# AnalogADCs.net
KiCad netlist of a schematic drawn in Altium Designer
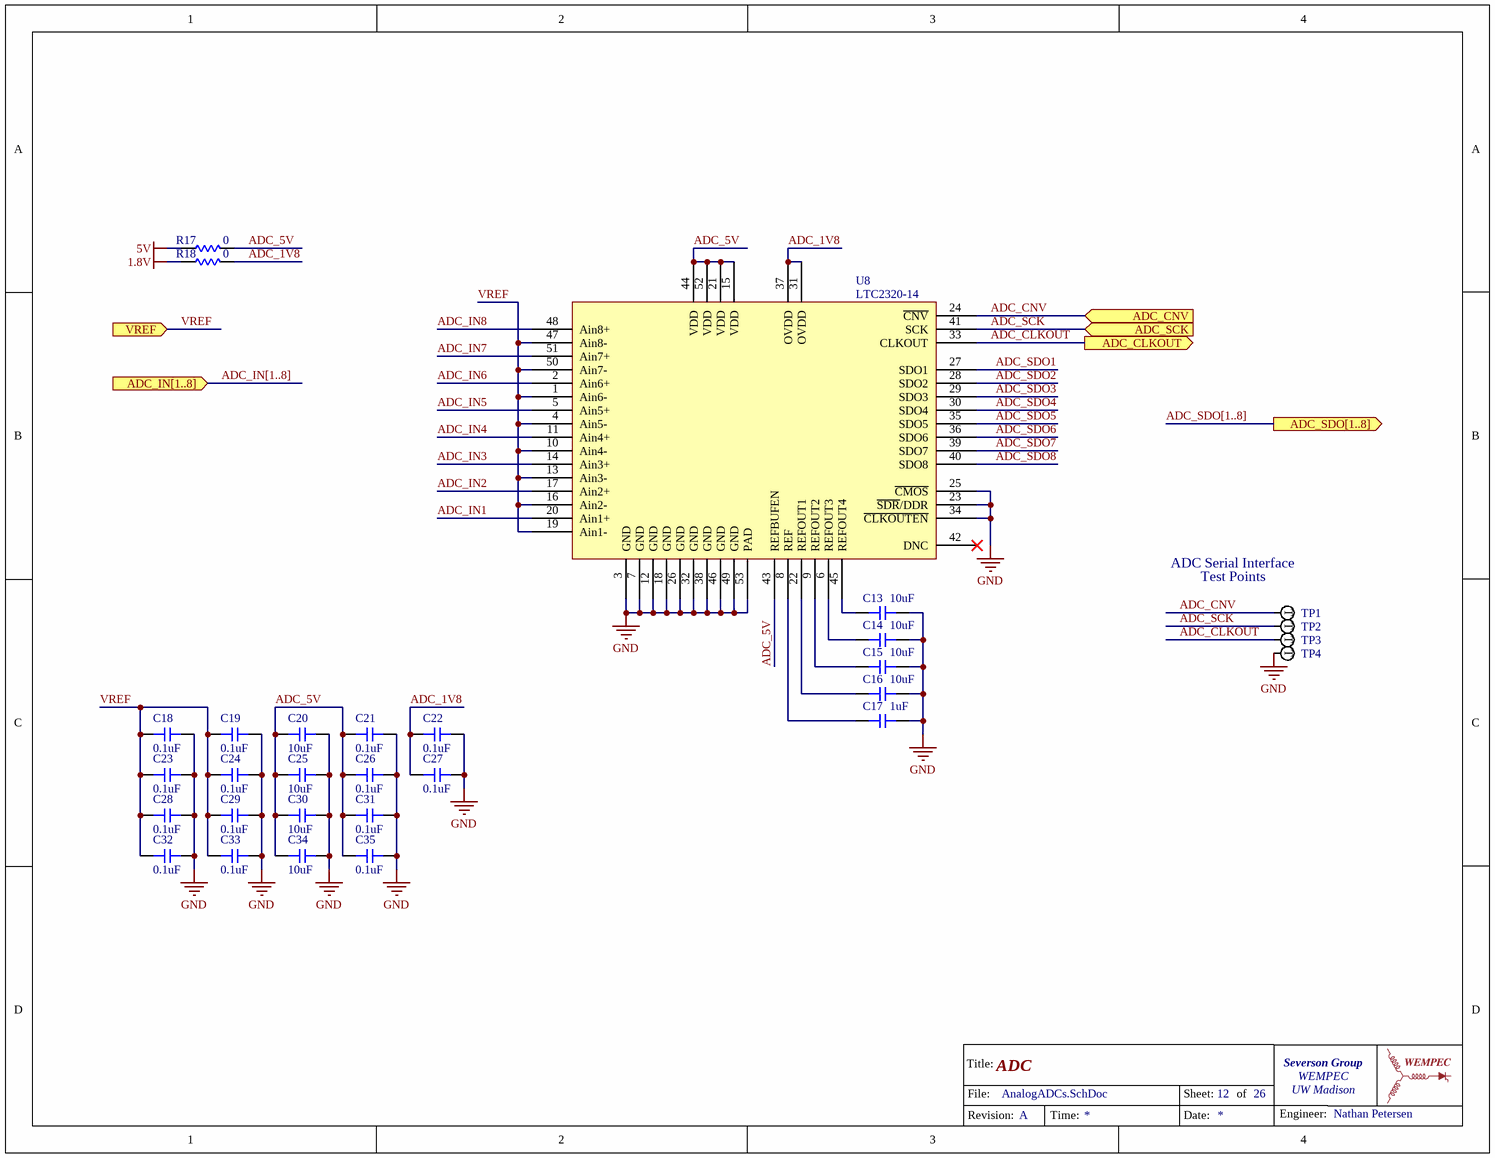
[diagram p0: AnalogADCs.SchDoc]

(export (version "E")
  (design (tool "Eeschema 10.0.6"))
  (components
    (comp (ref "C13")
      (value "10uF")
      (footprint "AMDC:0603-CAP")
      (description "Capacitor")
      (libsource (lib "AMDC") (part "Capacitor"))
    )
    (comp (ref "C14")
      (value "10uF")
      (footprint "AMDC:0603-CAP")
      (description "Capacitor")
      (libsource (lib "AMDC") (part "Capacitor"))
    )
    (comp (ref "C15")
      (value "10uF")
      (footprint "AMDC:0603-CAP")
      (description "Capacitor")
      (libsource (lib "AMDC") (part "Capacitor"))
    )
    (comp (ref "C16")
      (value "10uF")
      (footprint "AMDC:0603-CAP")
      (description "Capacitor")
      (libsource (lib "AMDC") (part "Capacitor"))
    )
    (comp (ref "C17")
      (value "1uF")
      (footprint "AMDC:0603-CAP")
      (description "Capacitor")
      (libsource (lib "AMDC") (part "Capacitor"))
    )
    (comp (ref "C18")
      (value "0.1uF")
      (footprint "AMDC:0603-CAP")
      (description "Capacitor")
      (libsource (lib "AMDC") (part "Capacitor"))
    )
    (comp (ref "C19")
      (value "0.1uF")
      (footprint "AMDC:0603-CAP")
      (description "Capacitor")
      (libsource (lib "AMDC") (part "Capacitor"))
    )
    (comp (ref "C20")
      (value "10uF")
      (footprint "AMDC:0603-CAP")
      (description "Capacitor")
      (libsource (lib "AMDC") (part "Capacitor"))
    )
    (comp (ref "C21")
      (value "0.1uF")
      (footprint "AMDC:0603-CAP")
      (description "Capacitor")
      (libsource (lib "AMDC") (part "Capacitor"))
    )
    (comp (ref "C22")
      (value "0.1uF")
      (footprint "AMDC:0603-CAP")
      (description "Capacitor")
      (libsource (lib "AMDC") (part "Capacitor"))
    )
    (comp (ref "C23")
      (value "0.1uF")
      (footprint "AMDC:0603-CAP")
      (description "Capacitor")
      (libsource (lib "AMDC") (part "Capacitor"))
    )
    (comp (ref "C24")
      (value "0.1uF")
      (footprint "AMDC:0603-CAP")
      (description "Capacitor")
      (libsource (lib "AMDC") (part "Capacitor"))
    )
    (comp (ref "C25")
      (value "10uF")
      (footprint "AMDC:0603-CAP")
      (description "Capacitor")
      (libsource (lib "AMDC") (part "Capacitor"))
    )
    (comp (ref "C26")
      (value "0.1uF")
      (footprint "AMDC:0603-CAP")
      (description "Capacitor")
      (libsource (lib "AMDC") (part "Capacitor"))
    )
    (comp (ref "C27")
      (value "0.1uF")
      (footprint "AMDC:0603-CAP")
      (description "Capacitor")
      (libsource (lib "AMDC") (part "Capacitor"))
    )
    (comp (ref "C28")
      (value "0.1uF")
      (footprint "AMDC:0603-CAP")
      (description "Capacitor")
      (libsource (lib "AMDC") (part "Capacitor"))
    )
    (comp (ref "C29")
      (value "0.1uF")
      (footprint "AMDC:0603-CAP")
      (description "Capacitor")
      (libsource (lib "AMDC") (part "Capacitor"))
    )
    (comp (ref "C30")
      (value "10uF")
      (footprint "AMDC:0603-CAP")
      (description "Capacitor")
      (libsource (lib "AMDC") (part "Capacitor"))
    )
    (comp (ref "C31")
      (value "0.1uF")
      (footprint "AMDC:0603-CAP")
      (description "Capacitor")
      (libsource (lib "AMDC") (part "Capacitor"))
    )
    (comp (ref "C32")
      (value "0.1uF")
      (footprint "AMDC:0603-CAP")
      (description "Capacitor")
      (libsource (lib "AMDC") (part "Capacitor"))
    )
    (comp (ref "C33")
      (value "0.1uF")
      (footprint "AMDC:0603-CAP")
      (description "Capacitor")
      (libsource (lib "AMDC") (part "Capacitor"))
    )
    (comp (ref "C34")
      (value "10uF")
      (footprint "AMDC:0603-CAP")
      (description "Capacitor")
      (libsource (lib "AMDC") (part "Capacitor"))
    )
    (comp (ref "C35")
      (value "0.1uF")
      (footprint "AMDC:0603-CAP")
      (description "Capacitor")
      (libsource (lib "AMDC") (part "Capacitor"))
    )
    (comp (ref "R17")
      (value "0")
      (footprint "AMDC:1206-RES")
      (description "Resistor")
      (libsource (lib "AMDC") (part "Resistor"))
    )
    (comp (ref "R18")
      (value "0")
      (footprint "AMDC:1206-RES")
      (description "Resistor")
      (libsource (lib "AMDC") (part "Resistor"))
    )
    (comp (ref "TP1")
      (value "Test Point")
      (footprint "AMDC:RCU-0C")
      (libsource (lib "AMDC") (part "Test Point"))
    )
    (comp (ref "TP2")
      (value "Test Point")
      (footprint "AMDC:RCU-0C")
      (libsource (lib "AMDC") (part "Test Point"))
    )
    (comp (ref "TP3")
      (value "Test Point")
      (footprint "AMDC:RCU-0C")
      (libsource (lib "AMDC") (part "Test Point"))
    )
    (comp (ref "TP4")
      (value "Test Point")
      (footprint "AMDC:RCU-0C")
      (libsource (lib "AMDC") (part "Test Point"))
    )
    (comp (ref "U8")
      (value "LTC2320-14")
      (footprint "AMDC:QFN50P700X800X80_HS-53N")
      (description "IC ADC 14BIT 1.5MSPS SAR 52QFN - 14 Bit Analog to Digital Converter 8 Input 4 SAR 52-QFN (7x8)")
      (libsource (lib "AMDC") (part "LTC2320-14"))
    )
  )
  (nets
    (net (code "1") (name "/ADC_1V8") (class "Default")
      (node (ref "C22") (pin "1") (pinfunction "1_1") (pintype "passive"))
      (node (ref "C27") (pin "1") (pinfunction "1_1") (pintype "passive"))
      (node (ref "R18") (pin "2") (pinfunction "2_2") (pintype "passive"))
      (node (ref "U8") (pin "31") (pinfunction "OVDD_31") (pintype "passive"))
      (node (ref "U8") (pin "37") (pinfunction "OVDD_37") (pintype "passive"))
    )
    (net (code "2") (name "/ADC_5V") (class "Default")
      (node (ref "C20") (pin "1") (pinfunction "1_1") (pintype "passive"))
      (node (ref "C21") (pin "1") (pinfunction "1_1") (pintype "passive"))
      (node (ref "C25") (pin "1") (pinfunction "1_1") (pintype "passive"))
      (node (ref "C26") (pin "1") (pinfunction "1_1") (pintype "passive"))
      (node (ref "C30") (pin "1") (pinfunction "1_1") (pintype "passive"))
      (node (ref "C31") (pin "1") (pinfunction "1_1") (pintype "passive"))
      (node (ref "C34") (pin "1") (pinfunction "1_1") (pintype "passive"))
      (node (ref "C35") (pin "1") (pinfunction "1_1") (pintype "passive"))
      (node (ref "R17") (pin "2") (pinfunction "2_2") (pintype "passive"))
      (node (ref "U8") (pin "15") (pinfunction "VDD_15") (pintype "passive"))
      (node (ref "U8") (pin "21") (pinfunction "VDD_21") (pintype "passive"))
      (node (ref "U8") (pin "43") (pinfunction "REFBUFEN_43") (pintype "passive"))
      (node (ref "U8") (pin "44") (pinfunction "VDD_44") (pintype "passive"))
      (node (ref "U8") (pin "52") (pinfunction "VDD_52") (pintype "passive"))
    )
    (net (code "3") (name "/ADC_CLKOUT") (class "Default")
      (node (ref "TP3") (pin "1") (pinfunction "1_1") (pintype "passive"))
      (node (ref "U8") (pin "33") (pinfunction "CLKOUT_33") (pintype "passive"))
    )
    (net (code "4") (name "/ADC_CNV") (class "Default")
      (node (ref "TP1") (pin "1") (pinfunction "1_1") (pintype "passive"))
      (node (ref "U8") (pin "24") (pinfunction "~{CNV}_24") (pintype "passive"))
    )
    (net (code "5") (name "/ADC_IN1") (class "Default")
      (node (ref "U8") (pin "20") (pinfunction "Ain1+_20") (pintype "passive"))
    )
    (net (code "6") (name "/ADC_IN2") (class "Default")
      (node (ref "U8") (pin "17") (pinfunction "Ain2+_17") (pintype "passive"))
    )
    (net (code "7") (name "/ADC_IN3") (class "Default")
      (node (ref "U8") (pin "14") (pinfunction "Ain3+_14") (pintype "passive"))
    )
    (net (code "8") (name "/ADC_IN4") (class "Default")
      (node (ref "U8") (pin "11") (pinfunction "Ain4+_11") (pintype "passive"))
    )
    (net (code "9") (name "/ADC_IN5") (class "Default")
      (node (ref "U8") (pin "5") (pinfunction "Ain5+_5") (pintype "passive"))
    )
    (net (code "10") (name "/ADC_IN6") (class "Default")
      (node (ref "U8") (pin "2") (pinfunction "Ain6+_2") (pintype "passive"))
    )
    (net (code "11") (name "/ADC_IN7") (class "Default")
      (node (ref "U8") (pin "51") (pinfunction "Ain7+_51") (pintype "passive"))
    )
    (net (code "12") (name "/ADC_IN8") (class "Default")
      (node (ref "U8") (pin "48") (pinfunction "Ain8+_48") (pintype "passive"))
    )
    (net (code "14") (name "/ADC_SCK") (class "Default")
      (node (ref "TP2") (pin "1") (pinfunction "1_1") (pintype "passive"))
      (node (ref "U8") (pin "41") (pinfunction "SCK_41") (pintype "passive"))
    )
    (net (code "15") (name "/ADC_SDO1") (class "Default")
      (node (ref "U8") (pin "27") (pinfunction "SDO1_27") (pintype "passive"))
    )
    (net (code "16") (name "/ADC_SDO2") (class "Default")
      (node (ref "U8") (pin "28") (pinfunction "SDO2_28") (pintype "passive"))
    )
    (net (code "17") (name "/ADC_SDO3") (class "Default")
      (node (ref "U8") (pin "29") (pinfunction "SDO3_29") (pintype "passive"))
    )
    (net (code "18") (name "/ADC_SDO4") (class "Default")
      (node (ref "U8") (pin "30") (pinfunction "SDO4_30") (pintype "passive"))
    )
    (net (code "19") (name "/ADC_SDO5") (class "Default")
      (node (ref "U8") (pin "35") (pinfunction "SDO5_35") (pintype "passive"))
    )
    (net (code "20") (name "/ADC_SDO6") (class "Default")
      (node (ref "U8") (pin "36") (pinfunction "SDO6_36") (pintype "passive"))
    )
    (net (code "21") (name "/ADC_SDO7") (class "Default")
      (node (ref "U8") (pin "39") (pinfunction "SDO7_39") (pintype "passive"))
    )
    (net (code "22") (name "/ADC_SDO8") (class "Default")
      (node (ref "U8") (pin "40") (pinfunction "SDO8_40") (pintype "passive"))
    )
    (net (code "24") (name "/VREF") (class "Default")
      (node (ref "C18") (pin "1") (pinfunction "1_1") (pintype "passive"))
      (node (ref "C19") (pin "1") (pinfunction "1_1") (pintype "passive"))
      (node (ref "C23") (pin "1") (pinfunction "1_1") (pintype "passive"))
      (node (ref "C24") (pin "1") (pinfunction "1_1") (pintype "passive"))
      (node (ref "C28") (pin "1") (pinfunction "1_1") (pintype "passive"))
      (node (ref "C29") (pin "1") (pinfunction "1_1") (pintype "passive"))
      (node (ref "C32") (pin "1") (pinfunction "1_1") (pintype "passive"))
      (node (ref "C33") (pin "1") (pinfunction "1_1") (pintype "passive"))
      (node (ref "U8") (pin "1") (pinfunction "Ain6-_1") (pintype "passive"))
      (node (ref "U8") (pin "10") (pinfunction "Ain4-_10") (pintype "passive"))
      (node (ref "U8") (pin "13") (pinfunction "Ain3-_13") (pintype "passive"))
      (node (ref "U8") (pin "16") (pinfunction "Ain2-_16") (pintype "passive"))
      (node (ref "U8") (pin "19") (pinfunction "Ain1-_19") (pintype "passive"))
      (node (ref "U8") (pin "4") (pinfunction "Ain5-_4") (pintype "passive"))
      (node (ref "U8") (pin "47") (pinfunction "Ain8-_47") (pintype "passive"))
      (node (ref "U8") (pin "50") (pinfunction "Ain7-_50") (pintype "passive"))
    )
    (net (code "25") (name "1.8V") (class "Default")
      (node (ref "R18") (pin "1") (pinfunction "1_1") (pintype "passive"))
    )
    (net (code "26") (name "5V") (class "Default")
      (node (ref "R17") (pin "1") (pinfunction "1_1") (pintype "passive"))
    )
    (net (code "27") (name "GND") (class "Default")
      (node (ref "C13") (pin "2") (pinfunction "2_2") (pintype "passive"))
      (node (ref "C14") (pin "2") (pinfunction "2_2") (pintype "passive"))
      (node (ref "C15") (pin "2") (pinfunction "2_2") (pintype "passive"))
      (node (ref "C16") (pin "2") (pinfunction "2_2") (pintype "passive"))
      (node (ref "C17") (pin "2") (pinfunction "2_2") (pintype "passive"))
      (node (ref "C18") (pin "2") (pinfunction "2_2") (pintype "passive"))
      (node (ref "C19") (pin "2") (pinfunction "2_2") (pintype "passive"))
      (node (ref "C20") (pin "2") (pinfunction "2_2") (pintype "passive"))
      (node (ref "C21") (pin "2") (pinfunction "2_2") (pintype "passive"))
      (node (ref "C22") (pin "2") (pinfunction "2_2") (pintype "passive"))
      (node (ref "C23") (pin "2") (pinfunction "2_2") (pintype "passive"))
      (node (ref "C24") (pin "2") (pinfunction "2_2") (pintype "passive"))
      (node (ref "C25") (pin "2") (pinfunction "2_2") (pintype "passive"))
      (node (ref "C26") (pin "2") (pinfunction "2_2") (pintype "passive"))
      (node (ref "C27") (pin "2") (pinfunction "2_2") (pintype "passive"))
      (node (ref "C28") (pin "2") (pinfunction "2_2") (pintype "passive"))
      (node (ref "C29") (pin "2") (pinfunction "2_2") (pintype "passive"))
      (node (ref "C30") (pin "2") (pinfunction "2_2") (pintype "passive"))
      (node (ref "C31") (pin "2") (pinfunction "2_2") (pintype "passive"))
      (node (ref "C32") (pin "2") (pinfunction "2_2") (pintype "passive"))
      (node (ref "C33") (pin "2") (pinfunction "2_2") (pintype "passive"))
      (node (ref "C34") (pin "2") (pinfunction "2_2") (pintype "passive"))
      (node (ref "C35") (pin "2") (pinfunction "2_2") (pintype "passive"))
      (node (ref "TP4") (pin "1") (pinfunction "1_1") (pintype "passive"))
      (node (ref "U8") (pin "12") (pinfunction "GND_12") (pintype "passive"))
      (node (ref "U8") (pin "18") (pinfunction "GND_18") (pintype "passive"))
      (node (ref "U8") (pin "23") (pinfunction "~{SDR}/DDR_23") (pintype "passive"))
      (node (ref "U8") (pin "25") (pinfunction "~{CMOS}_25") (pintype "passive"))
      (node (ref "U8") (pin "26") (pinfunction "GND_26") (pintype "passive"))
      (node (ref "U8") (pin "3") (pinfunction "GND_3") (pintype "passive"))
      (node (ref "U8") (pin "32") (pinfunction "GND_32") (pintype "passive"))
      (node (ref "U8") (pin "34") (pinfunction "~{CLKOUTEN}_34") (pintype "passive"))
      (node (ref "U8") (pin "38") (pinfunction "GND_38") (pintype "passive"))
      (node (ref "U8") (pin "46") (pinfunction "GND_46") (pintype "passive"))
      (node (ref "U8") (pin "49") (pinfunction "GND_49") (pintype "passive"))
      (node (ref "U8") (pin "53") (pinfunction "PAD_53") (pintype "passive"))
      (node (ref "U8") (pin "7") (pinfunction "GND_7") (pintype "passive"))
    )
    (net (code "28") (name "Net-(U8-REF)") (class "Default")
      (node (ref "C17") (pin "1") (pinfunction "1_1") (pintype "passive"))
      (node (ref "U8") (pin "8") (pinfunction "REF_8") (pintype "passive"))
    )
    (net (code "29") (name "Net-(U8-REFOUT1)") (class "Default")
      (node (ref "C16") (pin "1") (pinfunction "1_1") (pintype "passive"))
      (node (ref "U8") (pin "22") (pinfunction "REFOUT1_22") (pintype "passive"))
    )
    (net (code "30") (name "Net-(U8-REFOUT2)") (class "Default")
      (node (ref "C15") (pin "1") (pinfunction "1_1") (pintype "passive"))
      (node (ref "U8") (pin "9") (pinfunction "REFOUT2_9") (pintype "passive"))
    )
    (net (code "31") (name "Net-(U8-REFOUT3)") (class "Default")
      (node (ref "C14") (pin "1") (pinfunction "1_1") (pintype "passive"))
      (node (ref "U8") (pin "6") (pinfunction "REFOUT3_6") (pintype "passive"))
    )
    (net (code "32") (name "Net-(U8-REFOUT4)") (class "Default")
      (node (ref "C13") (pin "1") (pinfunction "1_1") (pintype "passive"))
      (node (ref "U8") (pin "45") (pinfunction "REFOUT4_45") (pintype "passive"))
    )
    (net (code "33") (name "unconnected-(U8-DNC-Pad42)") (class "Default")
      (node (ref "U8") (pin "42") (pinfunction "DNC_42") (pintype "passive+no_connect"))
    )
  )
)
